# MCUandExtra.net
KiCad netlist of a schematic drawn in Altium Designer
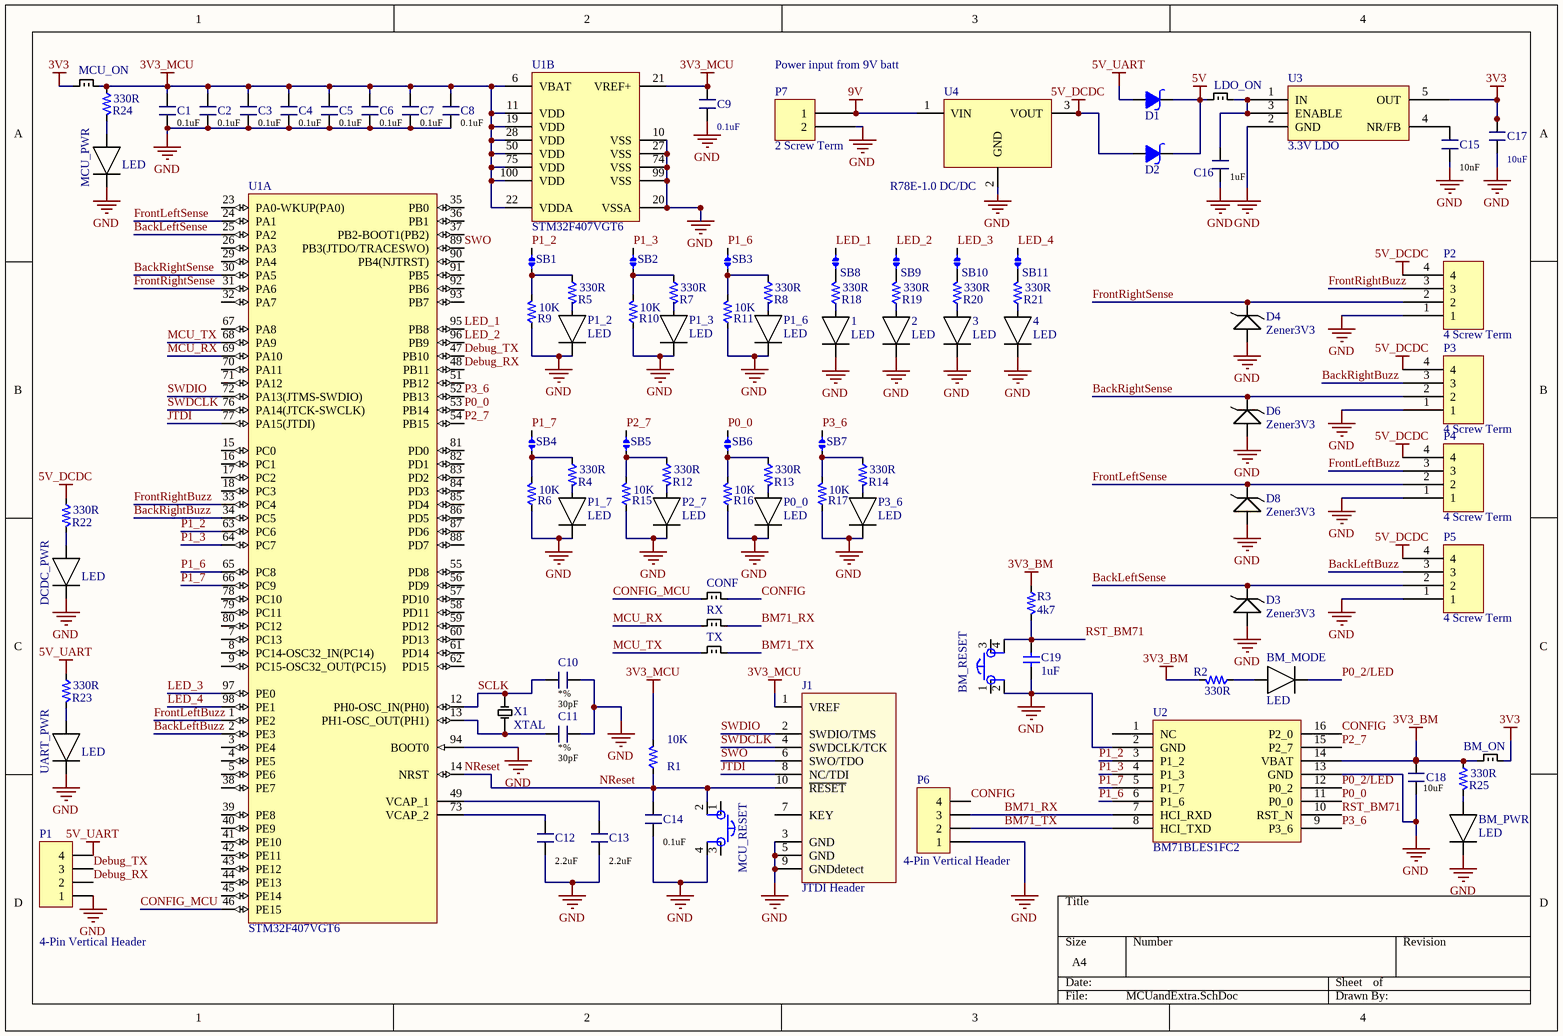
[diagram p0: MCUandExtra.SchDoc]

(export (version "E")
  (design (tool "Eeschema 10.0.6"))
  (components
    (comp (ref "1")
      (value "LED")
      (footprint "SMD_0603_LED")
      (libsource (lib "0603 LED") (part "SMD_0603_LED"))
    )
    (comp (ref "2")
      (value "LED")
      (footprint "SMD_0603_LED")
      (libsource (lib "0603 LED") (part "SMD_0603_LED"))
    )
    (comp (ref "3")
      (value "LED")
      (footprint "SMD_0603_LED")
      (libsource (lib "0603 LED") (part "SMD_0603_LED"))
    )
    (comp (ref "4")
      (value "LED")
      (footprint "SMD_0603_LED")
      (libsource (lib "0603 LED") (part "SMD_0603_LED"))
    )
    (comp (ref "BM_MODE")
      (value "LED")
      (footprint "SMD_0603_LED")
      (libsource (lib "0603 LED") (part "SMD_0603_LED"))
    )
    (comp (ref "BM_ON")
      (value "2.54Jump")
      (footprint "Jumper")
      (description "WM23943-ND")
      (libsource (lib "2.54HeaderJumper") (part "Jumper"))
    )
    (comp (ref "BM_PWR")
      (value "LED")
      (footprint "SMD_0603_LED")
      (libsource (lib "0603 LED") (part "SMD_0603_LED"))
    )
    (comp (ref "BM_RESET")
      (value "Tactile Switch")
      (footprint "C&K 4 pin Tactile Switch")
      (libsource (lib "C&K 4 Pin Tactile Switch") (part "C&K Tactile Switch"))
    )
    (comp (ref "C1")
      (value "SCH_GENERIC_CAPACITOR_0603")
      (footprint "PCB_GENERIC_SMD_0603")
      (description "Generic SMD capacitor 0603")
      (fields (field (name "TOLERANCE") "*%") (field (name "CAPACITANCE") "0.1uF"))
      (libsource (lib "Generic 0603 Capacitor") (part "SCH_GENERIC_CAPACITOR_0603"))
    )
    (comp (ref "C2")
      (value "SCH_GENERIC_CAPACITOR_0603")
      (footprint "PCB_GENERIC_SMD_0603")
      (description "Generic SMD capacitor 0603")
      (fields (field (name "TOLERANCE") "*%") (field (name "CAPACITANCE") "0.1uF"))
      (libsource (lib "Generic 0603 Capacitor") (part "SCH_GENERIC_CAPACITOR_0603"))
    )
    (comp (ref "C3")
      (value "SCH_GENERIC_CAPACITOR_0603")
      (footprint "PCB_GENERIC_SMD_0603")
      (description "Generic SMD capacitor 0603")
      (fields (field (name "TOLERANCE") "*%") (field (name "CAPACITANCE") "0.1uF"))
      (libsource (lib "Generic 0603 Capacitor") (part "SCH_GENERIC_CAPACITOR_0603"))
    )
    (comp (ref "C4")
      (value "SCH_GENERIC_CAPACITOR_0603")
      (footprint "PCB_GENERIC_SMD_0603")
      (description "Generic SMD capacitor 0603")
      (fields (field (name "TOLERANCE") "*%") (field (name "CAPACITANCE") "0.1uF"))
      (libsource (lib "Generic 0603 Capacitor") (part "SCH_GENERIC_CAPACITOR_0603"))
    )
    (comp (ref "C5")
      (value "SCH_GENERIC_CAPACITOR_0603")
      (footprint "PCB_GENERIC_SMD_0603")
      (description "Generic SMD capacitor 0603")
      (fields (field (name "TOLERANCE") "*%") (field (name "CAPACITANCE") "0.1uF"))
      (libsource (lib "Generic 0603 Capacitor") (part "SCH_GENERIC_CAPACITOR_0603"))
    )
    (comp (ref "C6")
      (value "SCH_GENERIC_CAPACITOR_0603")
      (footprint "PCB_GENERIC_SMD_0603")
      (description "Generic SMD capacitor 0603")
      (fields (field (name "TOLERANCE") "*%") (field (name "CAPACITANCE") "0.1uF"))
      (libsource (lib "Generic 0603 Capacitor") (part "SCH_GENERIC_CAPACITOR_0603"))
    )
    (comp (ref "C7")
      (value "SCH_GENERIC_CAPACITOR_0603")
      (footprint "PCB_GENERIC_SMD_0603")
      (description "Generic SMD capacitor 0603")
      (fields (field (name "TOLERANCE") "*%") (field (name "CAPACITANCE") "0.1uF"))
      (libsource (lib "Generic 0603 Capacitor") (part "SCH_GENERIC_CAPACITOR_0603"))
    )
    (comp (ref "C8")
      (value "SCH_GENERIC_CAPACITOR_0603")
      (footprint "PCB_GENERIC_SMD_0603")
      (description "Generic SMD capacitor 0603")
      (fields (field (name "TOLERANCE") "*%") (field (name "CAPACITANCE") "0.1uF"))
      (libsource (lib "Generic 0603 Capacitor") (part "SCH_GENERIC_CAPACITOR_0603"))
    )
    (comp (ref "C9")
      (value "SCH_GENERIC_CAPACITOR_0603")
      (footprint "PCB_GENERIC_SMD_0603")
      (description "Generic SMD capacitor 0603")
      (fields (field (name "CAPACITANCE") "0.1uF"))
      (libsource (lib "Generic 0603 Capacitor") (part "SCH_GENERIC_CAPACITOR_0603"))
    )
    (comp (ref "C10")
      (value "SCH_GENERIC_CAPACITOR_0603")
      (footprint "PCB_GENERIC_SMD_0603")
      (description "Generic SMD capacitor 0603")
      (fields (field (name "TOLERANCE") "*%") (field (name "CAPACITANCE") "30pF"))
      (libsource (lib "Capacitors") (part "SCH_GENERIC_CAPACITOR_0603"))
    )
    (comp (ref "C11")
      (value "SCH_GENERIC_CAPACITOR_0603")
      (footprint "PCB_GENERIC_SMD_0603")
      (description "Generic SMD capacitor 0603")
      (fields (field (name "TOLERANCE") "*%") (field (name "CAPACITANCE") "30pF"))
      (libsource (lib "Capacitors") (part "SCH_GENERIC_CAPACITOR_0603"))
    )
    (comp (ref "C12")
      (value "SCH_GENERIC_CAPACITOR_0603")
      (footprint "PCB_GENERIC_SMD_0603")
      (description "Generic SMD capacitor 0603")
      (fields (field (name "TOLERANCE") "*%") (field (name "CAPACITANCE") "2.2uF"))
      (libsource (lib "Capacitors") (part "SCH_GENERIC_CAPACITOR_0603"))
    )
    (comp (ref "C13")
      (value "SCH_GENERIC_CAPACITOR_0603")
      (footprint "PCB_GENERIC_SMD_0603")
      (description "Generic SMD capacitor 0603")
      (fields (field (name "TOLERANCE") "*%") (field (name "CAPACITANCE") "2.2uF"))
      (libsource (lib "Capacitors") (part "SCH_GENERIC_CAPACITOR_0603"))
    )
    (comp (ref "C14")
      (value "SCH_GENERIC_CAPACITOR_0603")
      (footprint "PCB_GENERIC_SMD_0603")
      (description "Generic SMD capacitor 0603")
      (fields (field (name "TOLERANCE") "*%") (field (name "CAPACITANCE") "0.1uF"))
      (libsource (lib "Capacitors") (part "SCH_GENERIC_CAPACITOR_0603"))
    )
    (comp (ref "C15")
      (value "SCH_GENERIC_CAPACITOR_0603")
      (footprint "PCB_GENERIC_SMD_0603")
      (description "Generic SMD capacitor 0603")
      (fields (field (name "CAPACITANCE") "10nF") (field (name "TOLERANCE") "*%"))
      (libsource (lib "Generic 0603 Capacitor") (part "SCH_GENERIC_CAPACITOR_0603"))
    )
    (comp (ref "C16")
      (value "SCH_GENERIC_CAPACITOR_0603")
      (footprint "PCB_GENERIC_SMD_0603")
      (description "Generic SMD capacitor 0603")
      (fields (field (name "CAPACITANCE") "1uF") (field (name "TOLERANCE") "*%"))
      (libsource (lib "Generic 0603 Capacitor") (part "SCH_GENERIC_CAPACITOR_0603"))
    )
    (comp (ref "C17")
      (value "SCH_GENERIC_CAPACITOR_0603")
      (footprint "PCB_GENERIC_SMD_0603")
      (description "Generic SMD capacitor 0603")
      (fields (field (name "CAPACITANCE") "10uF"))
      (libsource (lib "Generic 0603 Capacitor") (part "SCH_GENERIC_CAPACITOR_0603"))
    )
    (comp (ref "C18")
      (value "SCH_GENERIC_CAPACITOR_0603")
      (footprint "PCB_GENERIC_SMD_0603")
      (description "Generic SMD capacitor 0603")
      (fields (field (name "TOLERANCE") "*%") (field (name "CAPACITANCE") "10uF"))
      (libsource (lib "Capacitors") (part "SCH_GENERIC_CAPACITOR_0603"))
    )
    (comp (ref "C19")
      (value "1uF")
      (footprint "PCB_GENERIC_SMD_0603")
      (description "CAP CER 0603 1uF 16V X5R 20%")
      (fields (field (name "TOLERANCE") "20%") (field (name "VOLTAGE") "16V"))
      (libsource (lib "CAP-0603") (part "C060-0001U-00"))
    )
    (comp (ref "CONF")
      (value "2.54Jump")
      (footprint "Jumper")
      (description "WM23943-ND")
      (libsource (lib "2.54HeaderJumper") (part "Jumper"))
    )
    (comp (ref "D1")
      (value "ONSEMI_MBRM110LT1G")
      (footprint "ON Semi Schottky Diode - MBRM110LT1G")
      (description "DIODE SCHOTTKY 10V 1A")
      (libsource (lib "ON Semi Schottky Diode") (part "ONSEMI_MBRM110LT1G"))
    )
    (comp (ref "D2")
      (value "ONSEMI_MBRM110LT1G")
      (footprint "ON Semi Schottky Diode - MBRM110LT1G")
      (description "DIODE SCHOTTKY 10V 1A")
      (libsource (lib "ON Semi Schottky Diode") (part "ONSEMI_MBRM110LT1G"))
    )
    (comp (ref "D3")
      (value "Zener3V3")
      (footprint "Zener3V3")
      (description "DZ2W03300LCT-ND")
      (libsource (lib "Zener3V3") (part "DZ2W03300LCT-ND"))
    )
    (comp (ref "D4")
      (value "Zener3V3")
      (footprint "Zener3V3")
      (description "DZ2W03300LCT-ND")
      (libsource (lib "Zener3V3") (part "DZ2W03300LCT-ND"))
    )
    (comp (ref "D6")
      (value "Zener3V3")
      (footprint "Zener3V3")
      (description "DZ2W03300LCT-ND")
      (libsource (lib "Zener3V3") (part "DZ2W03300LCT-ND"))
    )
    (comp (ref "D8")
      (value "Zener3V3")
      (footprint "Zener3V3")
      (description "DZ2W03300LCT-ND")
      (libsource (lib "Zener3V3") (part "DZ2W03300LCT-ND"))
    )
    (comp (ref "DCDC_PWR")
      (value "LED")
      (footprint "SMD_0603_LED")
      (libsource (lib "0603 LED") (part "SMD_0603_LED"))
    )
    (comp (ref "J1")
      (value "JTDI Header")
      (footprint "CONN-50mil-10POS-SMD")
      (description "ARM Cortex-M 10pin connector,shrouded,SMT")
      (libsource (lib "CONN-50mil-cortexM") (part "conn_0.050{dblquote}_cortexM"))
    )
    (comp (ref "LDO_ON")
      (value "2.54Jump")
      (footprint "Jumper")
      (description "WM23943-ND")
      (libsource (lib "2.54HeaderJumper") (part "Jumper"))
    )
    (comp (ref "MCU_ON")
      (value "2.54Jump")
      (footprint "Jumper")
      (description "WM23943-ND")
      (libsource (lib "2.54HeaderJumper") (part "Jumper"))
    )
    (comp (ref "MCU_PWR")
      (value "LED")
      (footprint "SMD_0603_LED")
      (libsource (lib "0603 LED") (part "SMD_0603_LED"))
    )
    (comp (ref "MCU_RESET")
      (value "Tactile Switch")
      (footprint "C&K 4 pin Tactile Switch")
      (libsource (lib "C&K 4 Pin Tactile Switch") (part "C&K Tactile Switch"))
    )
    (comp (ref "P0_0")
      (value "LED")
      (footprint "SMD_0603_LED")
      (libsource (lib "0603 LED") (part "SMD_0603_LED"))
    )
    (comp (ref "P1")
      (value "4-Pin Vertical Header")
      (footprint "4-Pin Vertical Header")
      (fields (field (name "MANUFACTURER") "Sullins"))
      (libsource (lib "4 Pin 100 mil Vertical Header - Through Hole") (part "4-Pin Vertical Header"))
    )
    (comp (ref "P1_2")
      (value "LED")
      (footprint "SMD_0603_LED")
      (libsource (lib "0603 LED") (part "SMD_0603_LED"))
    )
    (comp (ref "P1_3")
      (value "LED")
      (footprint "SMD_0603_LED")
      (libsource (lib "0603 LED") (part "SMD_0603_LED"))
    )
    (comp (ref "P1_6")
      (value "LED")
      (footprint "SMD_0603_LED")
      (libsource (lib "0603 LED") (part "SMD_0603_LED"))
    )
    (comp (ref "P1_7")
      (value "LED")
      (footprint "SMD_0603_LED")
      (libsource (lib "0603 LED") (part "SMD_0603_LED"))
    )
    (comp (ref "P2")
      (value "4 Screw Term")
      (footprint "4 Pin Screw Terminal")
      (description "1297-1110-1-ND")
      (libsource (lib "4_Pin_ScrewTerm") (part "1297-1110-1-ND"))
    )
    (comp (ref "P2_7")
      (value "LED")
      (footprint "SMD_0603_LED")
      (libsource (lib "0603 LED") (part "SMD_0603_LED"))
    )
    (comp (ref "P3")
      (value "4 Screw Term")
      (footprint "4 Pin Screw Terminal")
      (description "1297-1110-1-ND")
      (libsource (lib "4_Pin_ScrewTerm") (part "1297-1110-1-ND"))
    )
    (comp (ref "P3_6")
      (value "LED")
      (footprint "SMD_0603_LED")
      (libsource (lib "0603 LED") (part "SMD_0603_LED"))
    )
    (comp (ref "P4")
      (value "4 Screw Term")
      (footprint "4 Pin Screw Terminal")
      (description "1297-1110-1-ND")
      (libsource (lib "4_Pin_ScrewTerm") (part "1297-1110-1-ND"))
    )
    (comp (ref "P5")
      (value "4 Screw Term")
      (footprint "4 Pin Screw Terminal")
      (description "1297-1110-1-ND")
      (libsource (lib "4_Pin_ScrewTerm") (part "1297-1110-1-ND"))
    )
    (comp (ref "P6")
      (value "4-Pin Vertical Header")
      (footprint "4-Pin Vertical Header")
      (fields (field (name "MANUFACTURER") "Sullins"))
      (libsource (lib "4 Pin 100 mil Vertical Header - Through Hole") (part "4-Pin Vertical Header"))
    )
    (comp (ref "P7")
      (value "2 Screw Term")
      (footprint "PCBComponent_1")
      (libsource (lib "2_Pin_ScrewTerm") (part "2 Screw Term"))
    )
    (comp (ref "R1")
      (value "SCH_GENERIC_RESISTOR_0603")
      (footprint "PCB_GENERIC_SMD_0603")
      (description "Generic SMD resistor 0603")
      (fields (field (name "RESISTANCE") "10K"))
      (libsource (lib "Resistors") (part "SCH_GENERIC_RESISTOR_0603"))
    )
    (comp (ref "R2")
      (value "SCH_GENERIC_RESISTOR_0603")
      (footprint "PCB_GENERIC_SMD_0603")
      (description "Generic SMD resistor 0603")
      (fields (field (name "RESISTANCE") "330R"))
      (libsource (lib "Resistors") (part "SCH_GENERIC_RESISTOR_0603"))
    )
    (comp (ref "R3")
      (value "SCH_GENERIC_RESISTOR_0603")
      (footprint "PCB_GENERIC_SMD_0603")
      (description "Generic SMD resistor 0603")
      (fields (field (name "RESISTANCE") "4k7"))
      (libsource (lib "Resistors") (part "SCH_GENERIC_RESISTOR_0603"))
    )
    (comp (ref "R4")
      (value "SCH_GENERIC_RESISTOR_0603")
      (footprint "PCB_GENERIC_SMD_0603")
      (description "Generic SMD resistor 0603")
      (fields (field (name "RESISTANCE") "330R"))
      (libsource (lib "Generic 0603 Resistor") (part "SCH_GENERIC_RESISTOR_0603"))
    )
    (comp (ref "R5")
      (value "SCH_GENERIC_RESISTOR_0603")
      (footprint "PCB_GENERIC_SMD_0603")
      (description "Generic SMD resistor 0603")
      (fields (field (name "RESISTANCE") "330R"))
      (libsource (lib "Generic 0603 Resistor") (part "SCH_GENERIC_RESISTOR_0603"))
    )
    (comp (ref "R6")
      (value "SCH_GENERIC_RESISTOR_0603")
      (footprint "PCB_GENERIC_SMD_0603")
      (description "Generic SMD resistor 0603")
      (fields (field (name "RESISTANCE") "10K"))
      (libsource (lib "Generic 0603 Resistor") (part "SCH_GENERIC_RESISTOR_0603"))
    )
    (comp (ref "R7")
      (value "SCH_GENERIC_RESISTOR_0603")
      (footprint "PCB_GENERIC_SMD_0603")
      (description "Generic SMD resistor 0603")
      (fields (field (name "RESISTANCE") "330R"))
      (libsource (lib "Generic 0603 Resistor") (part "SCH_GENERIC_RESISTOR_0603"))
    )
    (comp (ref "R8")
      (value "SCH_GENERIC_RESISTOR_0603")
      (footprint "PCB_GENERIC_SMD_0603")
      (description "Generic SMD resistor 0603")
      (fields (field (name "RESISTANCE") "330R"))
      (libsource (lib "Generic 0603 Resistor") (part "SCH_GENERIC_RESISTOR_0603"))
    )
    (comp (ref "R9")
      (value "SCH_GENERIC_RESISTOR_0603")
      (footprint "PCB_GENERIC_SMD_0603")
      (description "Generic SMD resistor 0603")
      (fields (field (name "RESISTANCE") "10K"))
      (libsource (lib "Generic 0603 Resistor") (part "SCH_GENERIC_RESISTOR_0603"))
    )
    (comp (ref "R10")
      (value "SCH_GENERIC_RESISTOR_0603")
      (footprint "PCB_GENERIC_SMD_0603")
      (description "Generic SMD resistor 0603")
      (fields (field (name "RESISTANCE") "10K"))
      (libsource (lib "Generic 0603 Resistor") (part "SCH_GENERIC_RESISTOR_0603"))
    )
    (comp (ref "R11")
      (value "SCH_GENERIC_RESISTOR_0603")
      (footprint "PCB_GENERIC_SMD_0603")
      (description "Generic SMD resistor 0603")
      (fields (field (name "RESISTANCE") "10K"))
      (libsource (lib "Generic 0603 Resistor") (part "SCH_GENERIC_RESISTOR_0603"))
    )
    (comp (ref "R12")
      (value "SCH_GENERIC_RESISTOR_0603")
      (footprint "PCB_GENERIC_SMD_0603")
      (description "Generic SMD resistor 0603")
      (fields (field (name "RESISTANCE") "330R"))
      (libsource (lib "Generic 0603 Resistor") (part "SCH_GENERIC_RESISTOR_0603"))
    )
    (comp (ref "R13")
      (value "SCH_GENERIC_RESISTOR_0603")
      (footprint "PCB_GENERIC_SMD_0603")
      (description "Generic SMD resistor 0603")
      (fields (field (name "RESISTANCE") "330R"))
      (libsource (lib "Generic 0603 Resistor") (part "SCH_GENERIC_RESISTOR_0603"))
    )
    (comp (ref "R14")
      (value "SCH_GENERIC_RESISTOR_0603")
      (footprint "PCB_GENERIC_SMD_0603")
      (description "Generic SMD resistor 0603")
      (fields (field (name "RESISTANCE") "330R"))
      (libsource (lib "Generic 0603 Resistor") (part "SCH_GENERIC_RESISTOR_0603"))
    )
    (comp (ref "R15")
      (value "SCH_GENERIC_RESISTOR_0603")
      (footprint "PCB_GENERIC_SMD_0603")
      (description "Generic SMD resistor 0603")
      (fields (field (name "RESISTANCE") "10K"))
      (libsource (lib "Generic 0603 Resistor") (part "SCH_GENERIC_RESISTOR_0603"))
    )
    (comp (ref "R16")
      (value "SCH_GENERIC_RESISTOR_0603")
      (footprint "PCB_GENERIC_SMD_0603")
      (description "Generic SMD resistor 0603")
      (fields (field (name "RESISTANCE") "10K"))
      (libsource (lib "Generic 0603 Resistor") (part "SCH_GENERIC_RESISTOR_0603"))
    )
    (comp (ref "R17")
      (value "SCH_GENERIC_RESISTOR_0603")
      (footprint "PCB_GENERIC_SMD_0603")
      (description "Generic SMD resistor 0603")
      (fields (field (name "RESISTANCE") "10K"))
      (libsource (lib "Generic 0603 Resistor") (part "SCH_GENERIC_RESISTOR_0603"))
    )
    (comp (ref "R18")
      (value "SCH_GENERIC_RESISTOR_0603")
      (footprint "PCB_GENERIC_SMD_0603")
      (description "Generic SMD resistor 0603")
      (fields (field (name "RESISTANCE") "330R"))
      (libsource (lib "Generic 0603 Resistor") (part "SCH_GENERIC_RESISTOR_0603"))
    )
    (comp (ref "R19")
      (value "SCH_GENERIC_RESISTOR_0603")
      (footprint "PCB_GENERIC_SMD_0603")
      (description "Generic SMD resistor 0603")
      (fields (field (name "RESISTANCE") "330R"))
      (libsource (lib "Generic 0603 Resistor") (part "SCH_GENERIC_RESISTOR_0603"))
    )
    (comp (ref "R20")
      (value "SCH_GENERIC_RESISTOR_0603")
      (footprint "PCB_GENERIC_SMD_0603")
      (description "Generic SMD resistor 0603")
      (fields (field (name "RESISTANCE") "330R"))
      (libsource (lib "Generic 0603 Resistor") (part "SCH_GENERIC_RESISTOR_0603"))
    )
    (comp (ref "R21")
      (value "SCH_GENERIC_RESISTOR_0603")
      (footprint "PCB_GENERIC_SMD_0603")
      (description "Generic SMD resistor 0603")
      (fields (field (name "RESISTANCE") "330R"))
      (libsource (lib "Generic 0603 Resistor") (part "SCH_GENERIC_RESISTOR_0603"))
    )
    (comp (ref "R22")
      (value "SCH_GENERIC_RESISTOR_0603")
      (footprint "PCB_GENERIC_SMD_0603")
      (description "Generic SMD resistor 0603")
      (fields (field (name "RESISTANCE") "330R"))
      (libsource (lib "Generic 0603 Resistor") (part "SCH_GENERIC_RESISTOR_0603"))
    )
    (comp (ref "R23")
      (value "SCH_GENERIC_RESISTOR_0603")
      (footprint "PCB_GENERIC_SMD_0603")
      (description "Generic SMD resistor 0603")
      (fields (field (name "RESISTANCE") "330R"))
      (libsource (lib "Generic 0603 Resistor") (part "SCH_GENERIC_RESISTOR_0603"))
    )
    (comp (ref "R24")
      (value "SCH_GENERIC_RESISTOR_0603")
      (footprint "PCB_GENERIC_SMD_0603")
      (description "Generic SMD resistor 0603")
      (fields (field (name "RESISTANCE") "330R"))
      (libsource (lib "Generic 0603 Resistor") (part "SCH_GENERIC_RESISTOR_0603"))
    )
    (comp (ref "R25")
      (value "SCH_GENERIC_RESISTOR_0603")
      (footprint "PCB_GENERIC_SMD_0603")
      (description "Generic SMD resistor 0603")
      (fields (field (name "RESISTANCE") "330R"))
      (libsource (lib "Generic 0603 Resistor") (part "SCH_GENERIC_RESISTOR_0603"))
    )
    (comp (ref "RX")
      (value "2.54Jump")
      (footprint "Jumper")
      (description "WM23943-ND")
      (libsource (lib "2.54HeaderJumper") (part "Jumper"))
    )
    (comp (ref "SB1")
      (value "N/O")
      (footprint "SB_NO")
      (description "Solder Bridge, Normally Open")
      (libsource (lib "SolderJumper20mil") (part "SB_NO"))
    )
    (comp (ref "SB2")
      (value "N/O")
      (footprint "SB_NO")
      (description "Solder Bridge, Normally Open")
      (libsource (lib "SolderJumper20mil") (part "SB_NO"))
    )
    (comp (ref "SB3")
      (value "N/O")
      (footprint "SB_NO")
      (description "Solder Bridge, Normally Open")
      (libsource (lib "SolderJumper20mil") (part "SB_NO"))
    )
    (comp (ref "SB4")
      (value "N/O")
      (footprint "SB_NO")
      (description "Solder Bridge, Normally Open")
      (libsource (lib "SolderJumper20mil") (part "SB_NO"))
    )
    (comp (ref "SB5")
      (value "N/O")
      (footprint "SB_NO")
      (description "Solder Bridge, Normally Open")
      (libsource (lib "SolderJumper20mil") (part "SB_NO"))
    )
    (comp (ref "SB6")
      (value "N/O")
      (footprint "SB_NO")
      (description "Solder Bridge, Normally Open")
      (libsource (lib "SolderJumper20mil") (part "SB_NO"))
    )
    (comp (ref "SB7")
      (value "N/O")
      (footprint "SB_NO")
      (description "Solder Bridge, Normally Open")
      (libsource (lib "SolderJumper20mil") (part "SB_NO"))
    )
    (comp (ref "SB8")
      (value "N/O")
      (footprint "SB_NO")
      (description "Solder Bridge, Normally Open")
      (libsource (lib "SolderJumper20mil") (part "SB_NO"))
    )
    (comp (ref "SB9")
      (value "N/O")
      (footprint "SB_NO")
      (description "Solder Bridge, Normally Open")
      (libsource (lib "SolderJumper20mil") (part "SB_NO"))
    )
    (comp (ref "SB10")
      (value "N/O")
      (footprint "SB_NO")
      (description "Solder Bridge, Normally Open")
      (libsource (lib "SolderJumper20mil") (part "SB_NO"))
    )
    (comp (ref "SB11")
      (value "N/O")
      (footprint "SB_NO")
      (description "Solder Bridge, Normally Open")
      (libsource (lib "SolderJumper20mil") (part "SB_NO"))
    )
    (comp (ref "TX")
      (value "2.54Jump")
      (footprint "Jumper")
      (description "WM23943-ND")
      (libsource (lib "2.54HeaderJumper") (part "Jumper"))
    )
    (comp (ref "U1")
      (value "STM32F407VGT6")
      (footprint "STM-LQFP100_N")
      (fields (field (name "MANUFACTURER") "STMicroelectronics"))
      (libsource (lib "STMicroelectronics STM32 F4") (part "STM32F407VGT6"))
    )
    (comp (ref "U2")
      (value "BM71BLES1FC2")
      (footprint "BM71BLES1FC2")
      (description "BM71 Bluetooth Module")
      (libsource (lib "BM71BLES1FC2") (part "BM71 Bluetooth Module"))
    )
    (comp (ref "U3")
      (value "3.3V LDO")
      (footprint "SOT95P280X145-5N")
      (description "Linear Voltage Regulator IC Positive Fixed 1 Output 3.3V 400mA SOT-23-5")
      (libsource (lib "3V3LDO_TPS73633DBVR_SOT23-5") (part "3V3LDO_TPS73633DBVR_SOT23-5"))
    )
    (comp (ref "U4")
      (value "R78E-1.0 DC/DC")
      (footprint "R78-1.0")
      (libsource (lib "Recom R78E-1.0") (part "R78E-1.0"))
    )
    (comp (ref "UART_PWR")
      (value "LED")
      (footprint "SMD_0603_LED")
      (libsource (lib "0603 LED") (part "SMD_0603_LED"))
    )
    (comp (ref "X1") (value "XTAL") (footprint "CRYSTAL_8MHZ") (libsource (lib "Crystal") (part "Crystal")))
  )
  (nets
    (net (code "1") (name "/BM71_RX") (class "Default")
      (node (ref "P6") (pin "3") (pinfunction "3_3") (pintype "passive"))
      (node (ref "RX") (pin "2") (pinfunction "2_2") (pintype "passive"))
      (node (ref "U2") (pin "7") (pinfunction "HCI_RXD_7") (pintype "passive"))
    )
    (net (code "2") (name "/BM71_TX") (class "Default")
      (node (ref "P6") (pin "2") (pinfunction "2_2") (pintype "passive"))
      (node (ref "TX") (pin "2") (pinfunction "2_2") (pintype "passive"))
      (node (ref "U2") (pin "8") (pinfunction "HCI_TXD_8") (pintype "passive"))
    )
    (net (code "3") (name "/BackLeftBuzz") (class "Default")
      (node (ref "P5") (pin "3") (pinfunction "3_3") (pintype "passive"))
      (node (ref "U1") (pin "2") (pinfunction "PE3_2") (pintype "bidirectional"))
    )
    (net (code "4") (name "/BackLeftSense") (class "Default")
      (node (ref "D3") (pin "1") (pinfunction "1_1") (pintype "passive"))
      (node (ref "P5") (pin "2") (pinfunction "2_2") (pintype "passive"))
      (node (ref "U1") (pin "25") (pinfunction "PA2_25") (pintype "bidirectional"))
    )
    (net (code "5") (name "/BackRightBuzz") (class "Default")
      (node (ref "P3") (pin "3") (pinfunction "3_3") (pintype "passive"))
      (node (ref "U1") (pin "34") (pinfunction "PC5_34") (pintype "bidirectional"))
    )
    (net (code "6") (name "/BackRightSense") (class "Default")
      (node (ref "D6") (pin "1") (pinfunction "1_1") (pintype "passive"))
      (node (ref "P3") (pin "2") (pinfunction "2_2") (pintype "passive"))
      (node (ref "U1") (pin "30") (pinfunction "PA5_30") (pintype "bidirectional"))
    )
    (net (code "7") (name "/CONFIG") (class "Default")
      (node (ref "CONF") (pin "2") (pinfunction "2_2") (pintype "passive"))
      (node (ref "P6") (pin "4") (pinfunction "4_4") (pintype "passive"))
      (node (ref "U2") (pin "16") (pinfunction "P2_0_16") (pintype "passive"))
    )
    (net (code "8") (name "/CONFIG_MCU") (class "Default")
      (node (ref "CONF") (pin "1") (pinfunction "1_1") (pintype "passive"))
      (node (ref "U1") (pin "46") (pinfunction "PE15_46") (pintype "bidirectional"))
    )
    (net (code "9") (name "/Debug_RX") (class "Default")
      (node (ref "P1") (pin "2") (pinfunction "2_2") (pintype "passive"))
      (node (ref "U1") (pin "48") (pinfunction "PB11_48") (pintype "bidirectional"))
    )
    (net (code "10") (name "/Debug_TX") (class "Default")
      (node (ref "P1") (pin "3") (pinfunction "3_3") (pintype "passive"))
      (node (ref "U1") (pin "47") (pinfunction "PB10_47") (pintype "bidirectional"))
    )
    (net (code "11") (name "/FrontLeftBuzz") (class "Default")
      (node (ref "P4") (pin "3") (pinfunction "3_3") (pintype "passive"))
      (node (ref "U1") (pin "1") (pinfunction "PE2_1") (pintype "bidirectional"))
    )
    (net (code "12") (name "/FrontLeftSense") (class "Default")
      (node (ref "D8") (pin "1") (pinfunction "1_1") (pintype "passive"))
      (node (ref "P4") (pin "2") (pinfunction "2_2") (pintype "passive"))
      (node (ref "U1") (pin "24") (pinfunction "PA1_24") (pintype "bidirectional"))
    )
    (net (code "13") (name "/FrontRightBuzz") (class "Default")
      (node (ref "P2") (pin "3") (pinfunction "3_3") (pintype "passive"))
      (node (ref "U1") (pin "33") (pinfunction "PC4_33") (pintype "bidirectional"))
    )
    (net (code "14") (name "/FrontRightSense") (class "Default")
      (node (ref "D4") (pin "1") (pinfunction "1_1") (pintype "passive"))
      (node (ref "P2") (pin "2") (pinfunction "2_2") (pintype "passive"))
      (node (ref "U1") (pin "31") (pinfunction "PA6_31") (pintype "bidirectional"))
    )
    (net (code "15") (name "/JTDI") (class "Default")
      (node (ref "J1") (pin "8") (pinfunction "NC/TDI_8") (pintype "passive"))
      (node (ref "U1") (pin "77") (pinfunction "PA15(JTDI)_77") (pintype "bidirectional"))
    )
    (net (code "16") (name "/LED_1") (class "Default")
      (node (ref "SB8") (pin "2") (pinfunction "2_2") (pintype "passive"))
      (node (ref "U1") (pin "95") (pinfunction "PB8_95") (pintype "bidirectional"))
    )
    (net (code "17") (name "/LED_2") (class "Default")
      (node (ref "SB9") (pin "2") (pinfunction "2_2") (pintype "passive"))
      (node (ref "U1") (pin "96") (pinfunction "PB9_96") (pintype "bidirectional"))
    )
    (net (code "18") (name "/LED_3") (class "Default")
      (node (ref "SB10") (pin "2") (pinfunction "2_2") (pintype "passive"))
      (node (ref "U1") (pin "97") (pinfunction "PE0_97") (pintype "bidirectional"))
    )
    (net (code "19") (name "/LED_4") (class "Default")
      (node (ref "SB11") (pin "2") (pinfunction "2_2") (pintype "passive"))
      (node (ref "U1") (pin "98") (pinfunction "PE1_98") (pintype "bidirectional"))
    )
    (net (code "20") (name "/MCU_RX") (class "Default")
      (node (ref "RX") (pin "1") (pinfunction "1_1") (pintype "passive"))
      (node (ref "U1") (pin "69") (pinfunction "PA10_69") (pintype "bidirectional"))
    )
    (net (code "21") (name "/MCU_TX") (class "Default")
      (node (ref "TX") (pin "1") (pinfunction "1_1") (pintype "passive"))
      (node (ref "U1") (pin "68") (pinfunction "PA9_68") (pintype "bidirectional"))
    )
    (net (code "22") (name "/NReset") (class "Default")
      (node (ref "C14") (pin "1") (pinfunction "1_1") (pintype "passive"))
      (node (ref "J1") (pin "10") (pinfunction "~{RESET}_10") (pintype "passive"))
      (node (ref "MCU_RESET") (pin "2") (pinfunction "2_2") (pintype "passive"))
      (node (ref "R1") (pin "1") (pinfunction "1_1") (pintype "passive"))
      (node (ref "U1") (pin "14") (pinfunction "NRST_14") (pintype "bidirectional"))
    )
    (net (code "23") (name "/P0_0") (class "Default")
      (node (ref "SB6") (pin "2") (pinfunction "2_2") (pintype "passive"))
      (node (ref "U1") (pin "53") (pinfunction "PB14_53") (pintype "bidirectional"))
      (node (ref "U2") (pin "11") (pinfunction "P0_0_11") (pintype "passive"))
    )
    (net (code "24") (name "/P0_2{slash}LED") (class "Default")
      (node (ref "BM_MODE") (pin "2") (pinfunction "2_2") (pintype "passive"))
      (node (ref "U2") (pin "12") (pinfunction "P0_2_12") (pintype "passive"))
    )
    (net (code "25") (name "/P1_2") (class "Default")
      (node (ref "SB1") (pin "2") (pinfunction "2_2") (pintype "passive"))
      (node (ref "U1") (pin "63") (pinfunction "PC6_63") (pintype "bidirectional"))
      (node (ref "U2") (pin "3") (pinfunction "P1_2_3") (pintype "passive"))
    )
    (net (code "26") (name "/P1_3") (class "Default")
      (node (ref "SB2") (pin "2") (pinfunction "2_2") (pintype "passive"))
      (node (ref "U1") (pin "64") (pinfunction "PC7_64") (pintype "bidirectional"))
      (node (ref "U2") (pin "4") (pinfunction "P1_3_4") (pintype "passive"))
    )
    (net (code "27") (name "/P1_6") (class "Default")
      (node (ref "SB3") (pin "2") (pinfunction "2_2") (pintype "passive"))
      (node (ref "U1") (pin "65") (pinfunction "PC8_65") (pintype "bidirectional"))
      (node (ref "U2") (pin "6") (pinfunction "P1_6_6") (pintype "passive"))
    )
    (net (code "28") (name "/P1_7") (class "Default")
      (node (ref "SB4") (pin "2") (pinfunction "2_2") (pintype "passive"))
      (node (ref "U1") (pin "66") (pinfunction "PC9_66") (pintype "bidirectional"))
      (node (ref "U2") (pin "5") (pinfunction "P1_7_5") (pintype "passive"))
    )
    (net (code "29") (name "/P2_7") (class "Default")
      (node (ref "SB5") (pin "2") (pinfunction "2_2") (pintype "passive"))
      (node (ref "U1") (pin "54") (pinfunction "PB15_54") (pintype "bidirectional"))
      (node (ref "U2") (pin "15") (pinfunction "P2_7_15") (pintype "passive"))
    )
    (net (code "30") (name "/P3_6") (class "Default")
      (node (ref "SB7") (pin "2") (pinfunction "2_2") (pintype "passive"))
      (node (ref "U1") (pin "52") (pinfunction "PB13_52") (pintype "bidirectional"))
      (node (ref "U2") (pin "9") (pinfunction "P3_6_9") (pintype "passive"))
    )
    (net (code "31") (name "/RST_BM71") (class "Default")
      (node (ref "BM_RESET") (pin "4") (pinfunction "4_4") (pintype "passive"))
      (node (ref "C19") (pin "2") (pinfunction "2_2") (pintype "passive"))
      (node (ref "R3") (pin "2") (pinfunction "2_2") (pintype "passive"))
      (node (ref "U2") (pin "10") (pinfunction "RST_N_10") (pintype "passive"))
    )
    (net (code "32") (name "/SCLK") (class "Default")
      (node (ref "C10") (pin "2") (pinfunction "2_2") (pintype "passive"))
      (node (ref "U1") (pin "12") (pinfunction "PH0-OSC_IN(PH0)_12") (pintype "bidirectional"))
      (node (ref "X1") (pin "1") (pintype "passive"))
    )
    (net (code "33") (name "/SWDCLK") (class "Default")
      (node (ref "J1") (pin "4") (pinfunction "SWDCLK/TCK_4") (pintype "passive"))
      (node (ref "U1") (pin "76") (pinfunction "PA14(JTCK-SWCLK)_76") (pintype "bidirectional"))
    )
    (net (code "34") (name "/SWDIO") (class "Default")
      (node (ref "J1") (pin "2") (pinfunction "SWDIO/TMS_2") (pintype "passive"))
      (node (ref "U1") (pin "72") (pinfunction "PA13(JTMS-SWDIO)_72") (pintype "bidirectional"))
    )
    (net (code "35") (name "/SWO") (class "Default")
      (node (ref "J1") (pin "6") (pinfunction "SWO/TDO_6") (pintype "passive"))
      (node (ref "U1") (pin "89") (pinfunction "PB3(JTDO/TRACESWO)_89") (pintype "bidirectional"))
    )
    (net (code "36") (name "3V3") (class "Default")
      (node (ref "BM_ON") (pin "2") (pinfunction "2_2") (pintype "passive"))
      (node (ref "C17") (pin "2") (pinfunction "2_2") (pintype "passive"))
      (node (ref "MCU_ON") (pin "1") (pinfunction "1_1") (pintype "passive"))
      (node (ref "U3") (pin "5") (pinfunction "OUT_5") (pintype "power_in"))
    )
    (net (code "37") (name "3V3_BM") (class "Default")
      (node (ref "BM_ON") (pin "1") (pinfunction "1_1") (pintype "passive"))
      (node (ref "C18") (pin "2") (pinfunction "2_2") (pintype "passive"))
      (node (ref "R2") (pin "2") (pinfunction "2_2") (pintype "passive"))
      (node (ref "R25") (pin "1") (pinfunction "1_1") (pintype "passive"))
      (node (ref "R3") (pin "1") (pinfunction "1_1") (pintype "passive"))
      (node (ref "U2") (pin "14") (pinfunction "VBAT_14") (pintype "passive"))
    )
    (net (code "38") (name "3V3_MCU") (class "Default")
      (node (ref "C1") (pin "2") (pinfunction "2_2") (pintype "passive"))
      (node (ref "C2") (pin "2") (pinfunction "2_2") (pintype "passive"))
      (node (ref "C3") (pin "2") (pinfunction "2_2") (pintype "passive"))
      (node (ref "C4") (pin "2") (pinfunction "2_2") (pintype "passive"))
      (node (ref "C5") (pin "2") (pinfunction "2_2") (pintype "passive"))
      (node (ref "C6") (pin "2") (pinfunction "2_2") (pintype "passive"))
      (node (ref "C7") (pin "2") (pinfunction "2_2") (pintype "passive"))
      (node (ref "C8") (pin "2") (pinfunction "2_2") (pintype "passive"))
      (node (ref "C9") (pin "2") (pinfunction "2_2") (pintype "passive"))
      (node (ref "J1") (pin "1") (pinfunction "VREF_1") (pintype "passive"))
      (node (ref "MCU_ON") (pin "2") (pinfunction "2_2") (pintype "passive"))
      (node (ref "R1") (pin "2") (pinfunction "2_2") (pintype "passive"))
      (node (ref "R24") (pin "1") (pinfunction "1_1") (pintype "passive"))
      (node (ref "U1") (pin "100") (pinfunction "VDD_100") (pintype "power_in"))
      (node (ref "U1") (pin "11") (pinfunction "VDD_11") (pintype "power_in"))
      (node (ref "U1") (pin "19") (pinfunction "VDD_19") (pintype "power_in"))
      (node (ref "U1") (pin "21") (pinfunction "VREF+_21") (pintype "power_in"))
      (node (ref "U1") (pin "22") (pinfunction "VDDA_22") (pintype "power_in"))
      (node (ref "U1") (pin "28") (pinfunction "VDD_28") (pintype "power_in"))
      (node (ref "U1") (pin "50") (pinfunction "VDD_50") (pintype "power_in"))
      (node (ref "U1") (pin "6") (pinfunction "VBAT_6") (pintype "power_in"))
      (node (ref "U1") (pin "75") (pinfunction "VDD_75") (pintype "power_in"))
    )
    (net (code "39") (name "5V") (class "Default")
      (node (ref "D1") (pin "1") (pinfunction "1_1") (pintype "passive"))
      (node (ref "D2") (pin "1") (pinfunction "1_1") (pintype "passive"))
      (node (ref "LDO_ON") (pin "1") (pinfunction "1_1") (pintype "passive"))
    )
    (net (code "40") (name "5V_DCDC") (class "Default")
      (node (ref "D2") (pin "2") (pinfunction "2_2") (pintype "passive"))
      (node (ref "P2") (pin "4") (pinfunction "4_4") (pintype "passive"))
      (node (ref "P3") (pin "4") (pinfunction "4_4") (pintype "passive"))
      (node (ref "P4") (pin "4") (pinfunction "4_4") (pintype "passive"))
      (node (ref "P5") (pin "4") (pinfunction "4_4") (pintype "passive"))
      (node (ref "R22") (pin "1") (pinfunction "1_1") (pintype "passive"))
      (node (ref "U4") (pin "3") (pinfunction "VOUT_3") (pintype "passive"))
    )
    (net (code "41") (name "5V_UART") (class "Default")
      (node (ref "D1") (pin "2") (pinfunction "2_2") (pintype "passive"))
      (node (ref "P1") (pin "4") (pinfunction "4_4") (pintype "passive"))
      (node (ref "R23") (pin "1") (pinfunction "1_1") (pintype "passive"))
    )
    (net (code "42") (name "9V") (class "Default")
      (node (ref "P7") (pin "1") (pinfunction "1_1") (pintype "passive"))
      (node (ref "U4") (pin "1") (pinfunction "VIN_1") (pintype "passive"))
    )
    (net (code "43") (name "GND") (class "Default")
      (node (ref "1") (pin "2") (pinfunction "2_2") (pintype "passive"))
      (node (ref "2") (pin "2") (pinfunction "2_2") (pintype "passive"))
      (node (ref "3") (pin "2") (pinfunction "2_2") (pintype "passive"))
      (node (ref "4") (pin "2") (pinfunction "2_2") (pintype "passive"))
      (node (ref "BM_PWR") (pin "2") (pinfunction "2_2") (pintype "passive"))
      (node (ref "BM_RESET") (pin "2") (pinfunction "2_2") (pintype "passive"))
      (node (ref "C1") (pin "1") (pinfunction "1_1") (pintype "passive"))
      (node (ref "C10") (pin "1") (pinfunction "1_1") (pintype "passive"))
      (node (ref "C11") (pin "1") (pinfunction "1_1") (pintype "passive"))
      (node (ref "C12") (pin "1") (pinfunction "1_1") (pintype "passive"))
      (node (ref "C13") (pin "1") (pinfunction "1_1") (pintype "passive"))
      (node (ref "C14") (pin "2") (pinfunction "2_2") (pintype "passive"))
      (node (ref "C15") (pin "1") (pinfunction "1_1") (pintype "passive"))
      (node (ref "C16") (pin "2") (pinfunction "2_2") (pintype "passive"))
      (node (ref "C17") (pin "1") (pinfunction "1_1") (pintype "passive"))
      (node (ref "C18") (pin "1") (pinfunction "1_1") (pintype "passive"))
      (node (ref "C19") (pin "1") (pinfunction "1_1") (pintype "passive"))
      (node (ref "C2") (pin "1") (pinfunction "1_1") (pintype "passive"))
      (node (ref "C3") (pin "1") (pinfunction "1_1") (pintype "passive"))
      (node (ref "C4") (pin "1") (pinfunction "1_1") (pintype "passive"))
      (node (ref "C5") (pin "1") (pinfunction "1_1") (pintype "passive"))
      (node (ref "C6") (pin "1") (pinfunction "1_1") (pintype "passive"))
      (node (ref "C7") (pin "1") (pinfunction "1_1") (pintype "passive"))
      (node (ref "C8") (pin "1") (pinfunction "1_1") (pintype "passive"))
      (node (ref "C9") (pin "1") (pinfunction "1_1") (pintype "passive"))
      (node (ref "D3") (pin "2") (pinfunction "2_2") (pintype "passive"))
      (node (ref "D4") (pin "2") (pinfunction "2_2") (pintype "passive"))
      (node (ref "D6") (pin "2") (pinfunction "2_2") (pintype "passive"))
      (node (ref "D8") (pin "2") (pinfunction "2_2") (pintype "passive"))
      (node (ref "DCDC_PWR") (pin "2") (pinfunction "2_2") (pintype "passive"))
      (node (ref "J1") (pin "3") (pinfunction "GND_3") (pintype "passive"))
      (node (ref "J1") (pin "5") (pinfunction "GND_5") (pintype "passive"))
      (node (ref "J1") (pin "9") (pinfunction "GNDdetect_9") (pintype "passive"))
      (node (ref "MCU_PWR") (pin "2") (pinfunction "2_2") (pintype "passive"))
      (node (ref "MCU_RESET") (pin "4") (pinfunction "4_4") (pintype "passive"))
      (node (ref "P0_0") (pin "2") (pinfunction "2_2") (pintype "passive"))
      (node (ref "P1") (pin "1") (pinfunction "1_1") (pintype "passive"))
      (node (ref "P1_2") (pin "2") (pinfunction "2_2") (pintype "passive"))
      (node (ref "P1_3") (pin "2") (pinfunction "2_2") (pintype "passive"))
      (node (ref "P1_6") (pin "2") (pinfunction "2_2") (pintype "passive"))
      (node (ref "P1_7") (pin "2") (pinfunction "2_2") (pintype "passive"))
      (node (ref "P2") (pin "1") (pinfunction "1_1") (pintype "passive"))
      (node (ref "P2_7") (pin "2") (pinfunction "2_2") (pintype "passive"))
      (node (ref "P3") (pin "1") (pinfunction "1_1") (pintype "passive"))
      (node (ref "P3_6") (pin "2") (pinfunction "2_2") (pintype "passive"))
      (node (ref "P4") (pin "1") (pinfunction "1_1") (pintype "passive"))
      (node (ref "P5") (pin "1") (pinfunction "1_1") (pintype "passive"))
      (node (ref "P6") (pin "1") (pinfunction "1_1") (pintype "passive"))
      (node (ref "P7") (pin "2") (pinfunction "2_2") (pintype "passive"))
      (node (ref "R10") (pin "1") (pinfunction "1_1") (pintype "passive"))
      (node (ref "R11") (pin "1") (pinfunction "1_1") (pintype "passive"))
      (node (ref "R15") (pin "1") (pinfunction "1_1") (pintype "passive"))
      (node (ref "R16") (pin "1") (pinfunction "1_1") (pintype "passive"))
      (node (ref "R17") (pin "1") (pinfunction "1_1") (pintype "passive"))
      (node (ref "R6") (pin "1") (pinfunction "1_1") (pintype "passive"))
      (node (ref "R9") (pin "1") (pinfunction "1_1") (pintype "passive"))
      (node (ref "U1") (pin "10") (pinfunction "VSS_10") (pintype "power_in"))
      (node (ref "U1") (pin "20") (pinfunction "VSSA_20") (pintype "power_in"))
      (node (ref "U1") (pin "27") (pinfunction "VSS_27") (pintype "power_in"))
      (node (ref "U1") (pin "74") (pinfunction "VSS_74") (pintype "power_in"))
      (node (ref "U1") (pin "94") (pinfunction "BOOT0_94") (pintype "input"))
      (node (ref "U1") (pin "99") (pinfunction "VSS_99") (pintype "power_in"))
      (node (ref "U2") (pin "13") (pinfunction "GND_13") (pintype "passive"))
      (node (ref "U2") (pin "2") (pinfunction "GND_2") (pintype "passive"))
      (node (ref "U3") (pin "2") (pinfunction "GND_2") (pintype "power_in"))
      (node (ref "U4") (pin "2") (pinfunction "GND_2") (pintype "passive"))
      (node (ref "UART_PWR") (pin "2") (pinfunction "2_2") (pintype "passive"))
    )
    (net (code "44") (name "Net-(1-Pad1)") (class "Default")
      (node (ref "1") (pin "1") (pinfunction "1_1") (pintype "passive"))
      (node (ref "R18") (pin "1") (pinfunction "1_1") (pintype "passive"))
    )
    (net (code "45") (name "Net-(2-Pad1)") (class "Default")
      (node (ref "2") (pin "1") (pinfunction "1_1") (pintype "passive"))
      (node (ref "R19") (pin "1") (pinfunction "1_1") (pintype "passive"))
    )
    (net (code "46") (name "Net-(3-Pad1)") (class "Default")
      (node (ref "3") (pin "1") (pinfunction "1_1") (pintype "passive"))
      (node (ref "R20") (pin "1") (pinfunction "1_1") (pintype "passive"))
    )
    (net (code "47") (name "Net-(4-Pad1)") (class "Default")
      (node (ref "4") (pin "1") (pinfunction "1_1") (pintype "passive"))
      (node (ref "R21") (pin "1") (pinfunction "1_1") (pintype "passive"))
    )
    (net (code "48") (name "Net-(BM_MODE-Pad1)") (class "Default")
      (node (ref "BM_MODE") (pin "1") (pinfunction "1_1") (pintype "passive"))
      (node (ref "R2") (pin "1") (pinfunction "1_1") (pintype "passive"))
    )
    (net (code "49") (name "Net-(BM_PWR-Pad1)") (class "Default")
      (node (ref "BM_PWR") (pin "1") (pinfunction "1_1") (pintype "passive"))
      (node (ref "R25") (pin "2") (pinfunction "2_2") (pintype "passive"))
    )
    (net (code "50") (name "Net-(DCDC_PWR-Pad1)") (class "Default")
      (node (ref "DCDC_PWR") (pin "1") (pinfunction "1_1") (pintype "passive"))
      (node (ref "R22") (pin "2") (pinfunction "2_2") (pintype "passive"))
    )
    (net (code "51") (name "Net-(MCU_PWR-Pad1)") (class "Default")
      (node (ref "MCU_PWR") (pin "1") (pinfunction "1_1") (pintype "passive"))
      (node (ref "R24") (pin "2") (pinfunction "2_2") (pintype "passive"))
    )
    (net (code "52") (name "Net-(P0_0-Pad1)") (class "Default")
      (node (ref "P0_0") (pin "1") (pinfunction "1_1") (pintype "passive"))
      (node (ref "R13") (pin "2") (pinfunction "2_2") (pintype "passive"))
    )
    (net (code "53") (name "Net-(P1_2-Pad1)") (class "Default")
      (node (ref "P1_2") (pin "1") (pinfunction "1_1") (pintype "passive"))
      (node (ref "R5") (pin "2") (pinfunction "2_2") (pintype "passive"))
    )
    (net (code "54") (name "Net-(P1_3-Pad1)") (class "Default")
      (node (ref "P1_3") (pin "1") (pinfunction "1_1") (pintype "passive"))
      (node (ref "R7") (pin "2") (pinfunction "2_2") (pintype "passive"))
    )
    (net (code "55") (name "Net-(P1_6-Pad1)") (class "Default")
      (node (ref "P1_6") (pin "1") (pinfunction "1_1") (pintype "passive"))
      (node (ref "R8") (pin "2") (pinfunction "2_2") (pintype "passive"))
    )
    (net (code "56") (name "Net-(P1_7-Pad1)") (class "Default")
      (node (ref "P1_7") (pin "1") (pinfunction "1_1") (pintype "passive"))
      (node (ref "R4") (pin "2") (pinfunction "2_2") (pintype "passive"))
    )
    (net (code "57") (name "Net-(P2_7-Pad1)") (class "Default")
      (node (ref "P2_7") (pin "1") (pinfunction "1_1") (pintype "passive"))
      (node (ref "R12") (pin "2") (pinfunction "2_2") (pintype "passive"))
    )
    (net (code "58") (name "Net-(P3_6-Pad1)") (class "Default")
      (node (ref "P3_6") (pin "1") (pinfunction "1_1") (pintype "passive"))
      (node (ref "R14") (pin "2") (pinfunction "2_2") (pintype "passive"))
    )
    (net (code "59") (name "Net-(R4-Pad1)") (class "Default")
      (node (ref "R4") (pin "1") (pinfunction "1_1") (pintype "passive"))
      (node (ref "R6") (pin "2") (pinfunction "2_2") (pintype "passive"))
      (node (ref "SB4") (pin "1") (pinfunction "1_1") (pintype "passive"))
    )
    (net (code "60") (name "Net-(R5-Pad1)") (class "Default")
      (node (ref "R5") (pin "1") (pinfunction "1_1") (pintype "passive"))
      (node (ref "R9") (pin "2") (pinfunction "2_2") (pintype "passive"))
      (node (ref "SB1") (pin "1") (pinfunction "1_1") (pintype "passive"))
    )
    (net (code "61") (name "Net-(R10-Pad2)") (class "Default")
      (node (ref "R10") (pin "2") (pinfunction "2_2") (pintype "passive"))
      (node (ref "R7") (pin "1") (pinfunction "1_1") (pintype "passive"))
      (node (ref "SB2") (pin "1") (pinfunction "1_1") (pintype "passive"))
    )
    (net (code "62") (name "Net-(R11-Pad2)") (class "Default")
      (node (ref "R11") (pin "2") (pinfunction "2_2") (pintype "passive"))
      (node (ref "R8") (pin "1") (pinfunction "1_1") (pintype "passive"))
      (node (ref "SB3") (pin "1") (pinfunction "1_1") (pintype "passive"))
    )
    (net (code "63") (name "Net-(R12-Pad1)") (class "Default")
      (node (ref "R12") (pin "1") (pinfunction "1_1") (pintype "passive"))
      (node (ref "R15") (pin "2") (pinfunction "2_2") (pintype "passive"))
      (node (ref "SB5") (pin "1") (pinfunction "1_1") (pintype "passive"))
    )
    (net (code "64") (name "Net-(R13-Pad1)") (class "Default")
      (node (ref "R13") (pin "1") (pinfunction "1_1") (pintype "passive"))
      (node (ref "R16") (pin "2") (pinfunction "2_2") (pintype "passive"))
      (node (ref "SB6") (pin "1") (pinfunction "1_1") (pintype "passive"))
    )
    (net (code "65") (name "Net-(R14-Pad1)") (class "Default")
      (node (ref "R14") (pin "1") (pinfunction "1_1") (pintype "passive"))
      (node (ref "R17") (pin "2") (pinfunction "2_2") (pintype "passive"))
      (node (ref "SB7") (pin "1") (pinfunction "1_1") (pintype "passive"))
    )
    (net (code "66") (name "Net-(R18-Pad2)") (class "Default")
      (node (ref "R18") (pin "2") (pinfunction "2_2") (pintype "passive"))
      (node (ref "SB8") (pin "1") (pinfunction "1_1") (pintype "passive"))
    )
    (net (code "67") (name "Net-(R19-Pad2)") (class "Default")
      (node (ref "R19") (pin "2") (pinfunction "2_2") (pintype "passive"))
      (node (ref "SB9") (pin "1") (pinfunction "1_1") (pintype "passive"))
    )
    (net (code "68") (name "Net-(R20-Pad2)") (class "Default")
      (node (ref "R20") (pin "2") (pinfunction "2_2") (pintype "passive"))
      (node (ref "SB10") (pin "1") (pinfunction "1_1") (pintype "passive"))
    )
    (net (code "69") (name "Net-(R21-Pad2)") (class "Default")
      (node (ref "R21") (pin "2") (pinfunction "2_2") (pintype "passive"))
      (node (ref "SB11") (pin "1") (pinfunction "1_1") (pintype "passive"))
    )
    (net (code "70") (name "Net-(R23-Pad2)") (class "Default")
      (node (ref "R23") (pin "2") (pinfunction "2_2") (pintype "passive"))
      (node (ref "UART_PWR") (pin "1") (pinfunction "1_1") (pintype "passive"))
    )
    (net (code "71") (name "Net-(U1A-PH1-OSC_OUT(PH1))") (class "Default")
      (node (ref "C11") (pin "2") (pinfunction "2_2") (pintype "passive"))
      (node (ref "U1") (pin "13") (pinfunction "PH1-OSC_OUT(PH1)_13") (pintype "bidirectional"))
      (node (ref "X1") (pin "2") (pintype "passive"))
    )
    (net (code "72") (name "Net-(U1A-VCAP_1)") (class "Default")
      (node (ref "C13") (pin "2") (pinfunction "2_2") (pintype "passive"))
      (node (ref "U1") (pin "49") (pinfunction "VCAP_1_49") (pintype "power_in"))
    )
    (net (code "73") (name "Net-(U1A-VCAP_2)") (class "Default")
      (node (ref "C12") (pin "2") (pinfunction "2_2") (pintype "passive"))
      (node (ref "U1") (pin "73") (pinfunction "VCAP_2_73") (pintype "power_in"))
    )
    (net (code "74") (name "Net-(U3-ENABLE)") (class "Default")
      (node (ref "C16") (pin "1") (pinfunction "1_1") (pintype "passive"))
      (node (ref "LDO_ON") (pin "2") (pinfunction "2_2") (pintype "passive"))
      (node (ref "U3") (pin "1") (pinfunction "IN_1") (pintype "power_in"))
      (node (ref "U3") (pin "3") (pinfunction "ENABLE_3") (pintype "power_in"))
    )
    (net (code "75") (name "Net-(U3-NR{slash}FB)") (class "Default")
      (node (ref "C15") (pin "2") (pinfunction "2_2") (pintype "passive"))
      (node (ref "U3") (pin "4") (pinfunction "NR/FB_4") (pintype "power_in"))
    )
    (net (code "76") (name "unconnected-(BM_RESET-Pad1)") (class "Default")
      (node (ref "BM_RESET") (pin "1") (pinfunction "1_1") (pintype "passive"))
    )
    (net (code "77") (name "unconnected-(BM_RESET-Pad3)") (class "Default")
      (node (ref "BM_RESET") (pin "3") (pinfunction "3_3") (pintype "passive"))
    )
    (net (code "78") (name "unconnected-(J1-KEY-Pad7)") (class "Default")
      (node (ref "J1") (pin "7") (pinfunction "KEY_7") (pintype "passive"))
    )
    (net (code "79") (name "unconnected-(MCU_RESET-Pad1)") (class "Default")
      (node (ref "MCU_RESET") (pin "1") (pinfunction "1_1") (pintype "passive"))
    )
    (net (code "80") (name "unconnected-(MCU_RESET-Pad3)") (class "Default")
      (node (ref "MCU_RESET") (pin "3") (pinfunction "3_3") (pintype "passive"))
    )
    (net (code "81") (name "unconnected-(U1A-PA0-WKUP(PA0)-Pad23)") (class "Default")
      (node (ref "U1") (pin "23") (pinfunction "PA0-WKUP(PA0)_23") (pintype "bidirectional"))
    )
    (net (code "82") (name "unconnected-(U1A-PA3-Pad26)") (class "Default")
      (node (ref "U1") (pin "26") (pinfunction "PA3_26") (pintype "bidirectional"))
    )
    (net (code "83") (name "unconnected-(U1A-PA4-Pad29)") (class "Default")
      (node (ref "U1") (pin "29") (pinfunction "PA4_29") (pintype "bidirectional"))
    )
    (net (code "84") (name "unconnected-(U1A-PA7-Pad32)") (class "Default")
      (node (ref "U1") (pin "32") (pinfunction "PA7_32") (pintype "bidirectional"))
    )
    (net (code "85") (name "unconnected-(U1A-PA8-Pad67)") (class "Default")
      (node (ref "U1") (pin "67") (pinfunction "PA8_67") (pintype "bidirectional"))
    )
    (net (code "86") (name "unconnected-(U1A-PA11-Pad70)") (class "Default")
      (node (ref "U1") (pin "70") (pinfunction "PA11_70") (pintype "bidirectional"))
    )
    (net (code "87") (name "unconnected-(U1A-PA12-Pad71)") (class "Default")
      (node (ref "U1") (pin "71") (pinfunction "PA12_71") (pintype "bidirectional"))
    )
    (net (code "88") (name "unconnected-(U1A-PB0-Pad35)") (class "Default")
      (node (ref "U1") (pin "35") (pinfunction "PB0_35") (pintype "bidirectional"))
    )
    (net (code "89") (name "unconnected-(U1A-PB1-Pad36)") (class "Default")
      (node (ref "U1") (pin "36") (pinfunction "PB1_36") (pintype "bidirectional"))
    )
    (net (code "90") (name "unconnected-(U1A-PB2-BOOT1(PB2)-Pad37)") (class "Default")
      (node (ref "U1") (pin "37") (pinfunction "PB2-BOOT1(PB2)_37") (pintype "bidirectional"))
    )
    (net (code "91") (name "unconnected-(U1A-PB4(NJTRST)-Pad90)") (class "Default")
      (node (ref "U1") (pin "90") (pinfunction "PB4(NJTRST)_90") (pintype "bidirectional"))
    )
    (net (code "92") (name "unconnected-(U1A-PB5-Pad91)") (class "Default")
      (node (ref "U1") (pin "91") (pinfunction "PB5_91") (pintype "bidirectional"))
    )
    (net (code "93") (name "unconnected-(U1A-PB6-Pad92)") (class "Default")
      (node (ref "U1") (pin "92") (pinfunction "PB6_92") (pintype "bidirectional"))
    )
    (net (code "94") (name "unconnected-(U1A-PB7-Pad93)") (class "Default")
      (node (ref "U1") (pin "93") (pinfunction "PB7_93") (pintype "bidirectional"))
    )
    (net (code "95") (name "unconnected-(U1A-PB12-Pad51)") (class "Default")
      (node (ref "U1") (pin "51") (pinfunction "PB12_51") (pintype "bidirectional"))
    )
    (net (code "96") (name "unconnected-(U1A-PC0-Pad15)") (class "Default")
      (node (ref "U1") (pin "15") (pinfunction "PC0_15") (pintype "bidirectional"))
    )
    (net (code "97") (name "unconnected-(U1A-PC1-Pad16)") (class "Default")
      (node (ref "U1") (pin "16") (pinfunction "PC1_16") (pintype "bidirectional"))
    )
    (net (code "98") (name "unconnected-(U1A-PC2-Pad17)") (class "Default")
      (node (ref "U1") (pin "17") (pinfunction "PC2_17") (pintype "bidirectional"))
    )
    (net (code "99") (name "unconnected-(U1A-PC3-Pad18)") (class "Default")
      (node (ref "U1") (pin "18") (pinfunction "PC3_18") (pintype "bidirectional"))
    )
    (net (code "100") (name "unconnected-(U1A-PC10-Pad78)") (class "Default")
      (node (ref "U1") (pin "78") (pinfunction "PC10_78") (pintype "bidirectional"))
    )
    (net (code "101") (name "unconnected-(U1A-PC11-Pad79)") (class "Default")
      (node (ref "U1") (pin "79") (pinfunction "PC11_79") (pintype "bidirectional"))
    )
    (net (code "102") (name "unconnected-(U1A-PC12-Pad80)") (class "Default")
      (node (ref "U1") (pin "80") (pinfunction "PC12_80") (pintype "bidirectional"))
    )
    (net (code "103") (name "unconnected-(U1A-PC13-Pad7)") (class "Default")
      (node (ref "U1") (pin "7") (pinfunction "PC13_7") (pintype "bidirectional"))
    )
    (net (code "104") (name "unconnected-(U1A-PC14-OSC32_IN(PC14)-Pad8)") (class "Default")
      (node (ref "U1") (pin "8") (pinfunction "PC14-OSC32_IN(PC14)_8") (pintype "bidirectional"))
    )
    (net (code "105") (name "unconnected-(U1A-PC15-OSC32_OUT(PC15)-Pad9)") (class "Default")
      (node (ref "U1") (pin "9") (pinfunction "PC15-OSC32_OUT(PC15)_9") (pintype "bidirectional"))
    )
    (net (code "106") (name "unconnected-(U1A-PD0-Pad81)") (class "Default")
      (node (ref "U1") (pin "81") (pinfunction "PD0_81") (pintype "bidirectional"))
    )
    (net (code "107") (name "unconnected-(U1A-PD1-Pad82)") (class "Default")
      (node (ref "U1") (pin "82") (pinfunction "PD1_82") (pintype "bidirectional"))
    )
    (net (code "108") (name "unconnected-(U1A-PD2-Pad83)") (class "Default")
      (node (ref "U1") (pin "83") (pinfunction "PD2_83") (pintype "bidirectional"))
    )
    (net (code "109") (name "unconnected-(U1A-PD3-Pad84)") (class "Default")
      (node (ref "U1") (pin "84") (pinfunction "PD3_84") (pintype "bidirectional"))
    )
    (net (code "110") (name "unconnected-(U1A-PD4-Pad85)") (class "Default")
      (node (ref "U1") (pin "85") (pinfunction "PD4_85") (pintype "bidirectional"))
    )
    (net (code "111") (name "unconnected-(U1A-PD5-Pad86)") (class "Default")
      (node (ref "U1") (pin "86") (pinfunction "PD5_86") (pintype "bidirectional"))
    )
    (net (code "112") (name "unconnected-(U1A-PD6-Pad87)") (class "Default")
      (node (ref "U1") (pin "87") (pinfunction "PD6_87") (pintype "bidirectional"))
    )
    (net (code "113") (name "unconnected-(U1A-PD7-Pad88)") (class "Default")
      (node (ref "U1") (pin "88") (pinfunction "PD7_88") (pintype "bidirectional"))
    )
    (net (code "114") (name "unconnected-(U1A-PD8-Pad55)") (class "Default")
      (node (ref "U1") (pin "55") (pinfunction "PD8_55") (pintype "bidirectional"))
    )
    (net (code "115") (name "unconnected-(U1A-PD9-Pad56)") (class "Default")
      (node (ref "U1") (pin "56") (pinfunction "PD9_56") (pintype "bidirectional"))
    )
    (net (code "116") (name "unconnected-(U1A-PD10-Pad57)") (class "Default")
      (node (ref "U1") (pin "57") (pinfunction "PD10_57") (pintype "bidirectional"))
    )
    (net (code "117") (name "unconnected-(U1A-PD11-Pad58)") (class "Default")
      (node (ref "U1") (pin "58") (pinfunction "PD11_58") (pintype "bidirectional"))
    )
    (net (code "118") (name "unconnected-(U1A-PD12-Pad59)") (class "Default")
      (node (ref "U1") (pin "59") (pinfunction "PD12_59") (pintype "bidirectional"))
    )
    (net (code "119") (name "unconnected-(U1A-PD13-Pad60)") (class "Default")
      (node (ref "U1") (pin "60") (pinfunction "PD13_60") (pintype "bidirectional"))
    )
    (net (code "120") (name "unconnected-(U1A-PD14-Pad61)") (class "Default")
      (node (ref "U1") (pin "61") (pinfunction "PD14_61") (pintype "bidirectional"))
    )
    (net (code "121") (name "unconnected-(U1A-PD15-Pad62)") (class "Default")
      (node (ref "U1") (pin "62") (pinfunction "PD15_62") (pintype "bidirectional"))
    )
    (net (code "122") (name "unconnected-(U1A-PE4-Pad3)") (class "Default")
      (node (ref "U1") (pin "3") (pinfunction "PE4_3") (pintype "bidirectional"))
    )
    (net (code "123") (name "unconnected-(U1A-PE5-Pad4)") (class "Default")
      (node (ref "U1") (pin "4") (pinfunction "PE5_4") (pintype "bidirectional"))
    )
    (net (code "124") (name "unconnected-(U1A-PE6-Pad5)") (class "Default")
      (node (ref "U1") (pin "5") (pinfunction "PE6_5") (pintype "bidirectional"))
    )
    (net (code "125") (name "unconnected-(U1A-PE7-Pad38)") (class "Default")
      (node (ref "U1") (pin "38") (pinfunction "PE7_38") (pintype "bidirectional"))
    )
    (net (code "126") (name "unconnected-(U1A-PE8-Pad39)") (class "Default")
      (node (ref "U1") (pin "39") (pinfunction "PE8_39") (pintype "bidirectional"))
    )
    (net (code "127") (name "unconnected-(U1A-PE9-Pad40)") (class "Default")
      (node (ref "U1") (pin "40") (pinfunction "PE9_40") (pintype "bidirectional"))
    )
    (net (code "128") (name "unconnected-(U1A-PE10-Pad41)") (class "Default")
      (node (ref "U1") (pin "41") (pinfunction "PE10_41") (pintype "bidirectional"))
    )
    (net (code "129") (name "unconnected-(U1A-PE11-Pad42)") (class "Default")
      (node (ref "U1") (pin "42") (pinfunction "PE11_42") (pintype "bidirectional"))
    )
    (net (code "130") (name "unconnected-(U1A-PE12-Pad43)") (class "Default")
      (node (ref "U1") (pin "43") (pinfunction "PE12_43") (pintype "bidirectional"))
    )
    (net (code "131") (name "unconnected-(U1A-PE13-Pad44)") (class "Default")
      (node (ref "U1") (pin "44") (pinfunction "PE13_44") (pintype "bidirectional"))
    )
    (net (code "132") (name "unconnected-(U1A-PE14-Pad45)") (class "Default")
      (node (ref "U1") (pin "45") (pinfunction "PE14_45") (pintype "bidirectional"))
    )
    (net (code "133") (name "unconnected-(U2-NC-Pad1)") (class "Default")
      (node (ref "U2") (pin "1") (pinfunction "NC_1") (pintype "passive"))
    )
  )
)
